# DSP_Block.net
KiCad netlist of a schematic drawn in Altium Designer
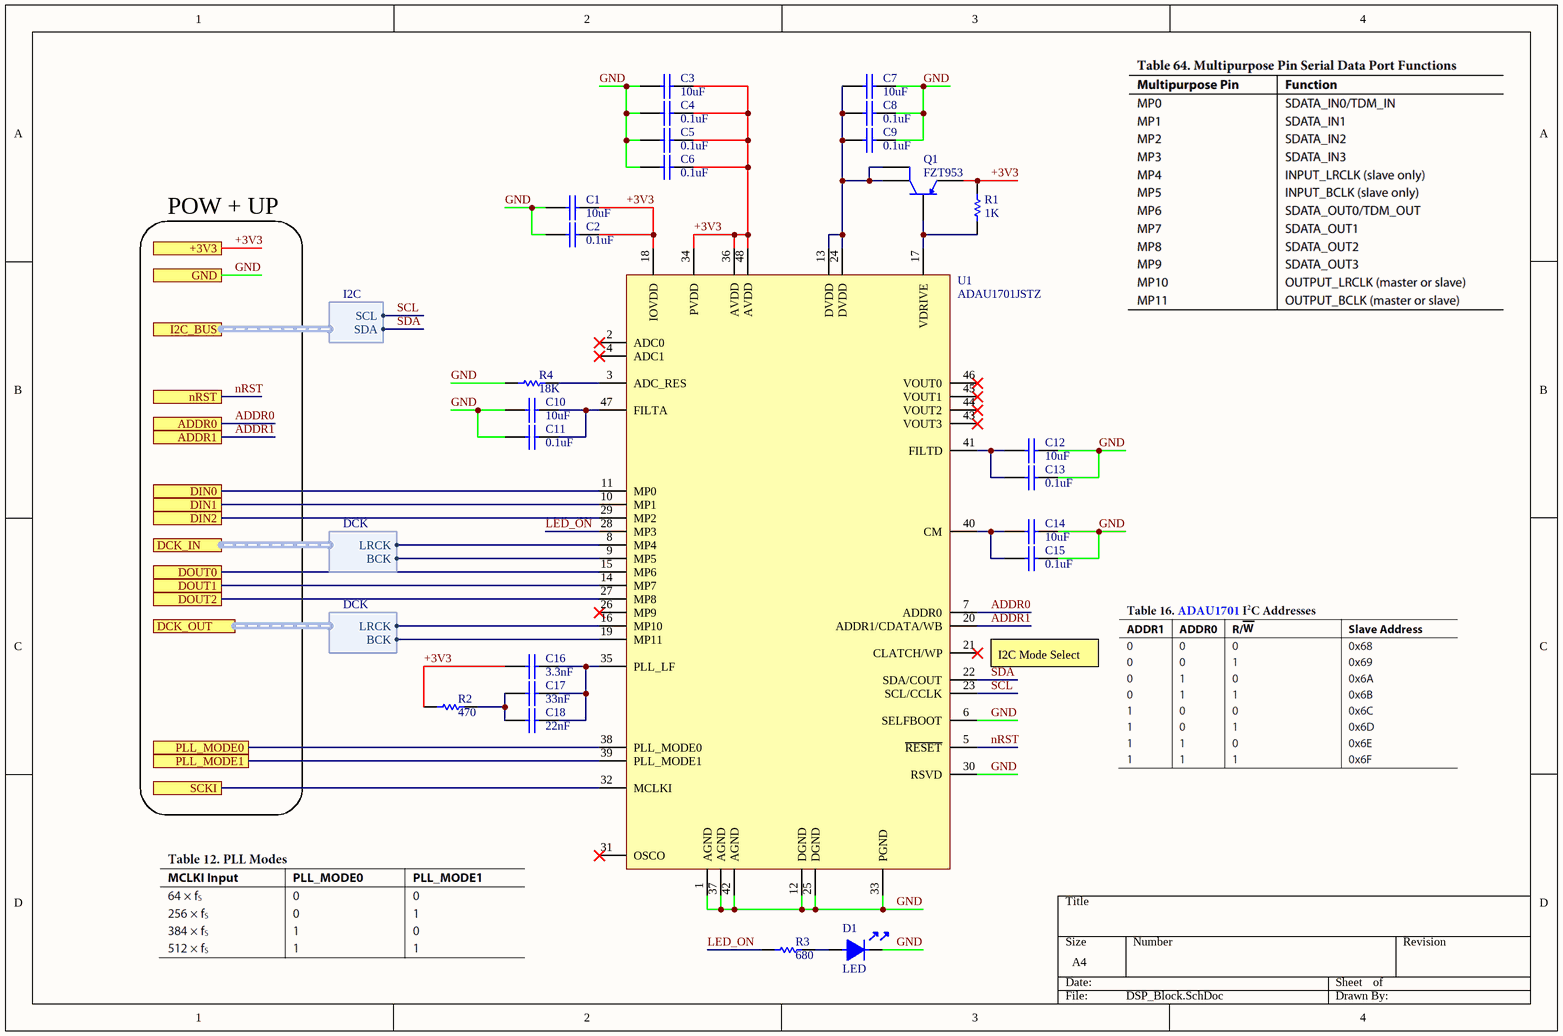
[diagram p0: DSP_Block.SchDoc]

(export (version "E")
  (design (tool "Eeschema 10.0.6"))
  (components
    (comp (ref "C1")
      (value "10uF")
      (footprint "0603-CAP-TDK")
      (libsource (lib "LIB2022 - Passives") (part "CAP-SMD"))
    )
    (comp (ref "C2")
      (value "0.1uF")
      (footprint "0402-CAP-TDK")
      (libsource (lib "LIB2022 - Passives") (part "CAP-SMD"))
    )
    (comp (ref "C3")
      (value "10uF")
      (footprint "0603-CAP-TDK")
      (libsource (lib "LIB2022 - Passives") (part "CAP-SMD"))
    )
    (comp (ref "C4")
      (value "0.1uF")
      (footprint "0402-CAP-TDK")
      (libsource (lib "LIB2022 - Passives") (part "CAP-SMD"))
    )
    (comp (ref "C5")
      (value "0.1uF")
      (footprint "0402-CAP-TDK")
      (libsource (lib "LIB2022 - Passives") (part "CAP-SMD"))
    )
    (comp (ref "C6")
      (value "0.1uF")
      (footprint "0402-CAP-TDK")
      (libsource (lib "LIB2022 - Passives") (part "CAP-SMD"))
    )
    (comp (ref "C7")
      (value "10uF")
      (footprint "0603-CAP-TDK")
      (libsource (lib "LIB2022 - Passives") (part "CAP-SMD"))
    )
    (comp (ref "C8")
      (value "0.1uF")
      (footprint "0402-CAP-TDK")
      (libsource (lib "LIB2022 - Passives") (part "CAP-SMD"))
    )
    (comp (ref "C9")
      (value "0.1uF")
      (footprint "0402-CAP-TDK")
      (libsource (lib "LIB2022 - Passives") (part "CAP-SMD"))
    )
    (comp (ref "C10")
      (value "10uF")
      (footprint "0603-CAP-TDK")
      (libsource (lib "LIB2022 - Passives") (part "CAP-SMD"))
    )
    (comp (ref "C11")
      (value "0.1uF")
      (footprint "0402-CAP-TDK")
      (libsource (lib "LIB2022 - Passives") (part "CAP-SMD"))
    )
    (comp (ref "C12")
      (value "10uF")
      (footprint "0603-CAP-TDK")
      (libsource (lib "LIB2022 - Passives") (part "CAP-SMD"))
    )
    (comp (ref "C13")
      (value "0.1uF")
      (footprint "0402-CAP-TDK")
      (libsource (lib "LIB2022 - Passives") (part "CAP-SMD"))
    )
    (comp (ref "C14")
      (value "10uF")
      (footprint "0603-CAP-TDK")
      (libsource (lib "LIB2022 - Passives") (part "CAP-SMD"))
    )
    (comp (ref "C15")
      (value "0.1uF")
      (footprint "0402-CAP-TDK")
      (libsource (lib "LIB2022 - Passives") (part "CAP-SMD"))
    )
    (comp (ref "C16")
      (value "3.3nF")
      (footprint "0402-CAP-TDK")
      (libsource (lib "LIB2022 - Passives") (part "CAP-SMD"))
    )
    (comp (ref "C17")
      (value "33nF")
      (footprint "0603-CAP-TDK")
      (libsource (lib "LIB2022 - Passives") (part "CAP-SMD"))
    )
    (comp (ref "C18")
      (value "22nF")
      (footprint "0603-CAP-TDK")
      (libsource (lib "LIB2022 - Passives") (part "CAP-SMD"))
    )
    (comp (ref "D1")
      (value "LED")
      (footprint "LED-0805")
      (libsource (lib "LIB2022 - Optoelectronics") (part "LED-SMD"))
    )
    (comp (ref "Q1")
      (value "FZT953")
      (footprint "SOT223-DN")
      (libsource (lib "LIB2022 - Semiconductors") (part "FZT953"))
    )
    (comp (ref "R1")
      (value "1K")
      (footprint "0402-RES-PANASONIC")
      (libsource (lib "LIB2022 - Passives") (part "RES-SMD"))
    )
    (comp (ref "R2")
      (value "470")
      (footprint "0402-RES-PANASONIC")
      (libsource (lib "LIB2022 - Passives") (part "RES-SMD"))
    )
    (comp (ref "R3")
      (value "680")
      (footprint "0402-RES-PANASONIC")
      (libsource (lib "LIB2022 - Passives") (part "RES-SMD"))
    )
    (comp (ref "R4")
      (value "18K")
      (footprint "0402-RES-PANASONIC")
      (libsource (lib "LIB2022 - Passives") (part "RES-SMD"))
    )
    (comp (ref "U1")
      (value "ADAU1701JSTZ")
      (footprint "LQFP-48 - ST-48")
      (description "SigmaDSP 28-/56-Bit Audio Processor with Two ADCs and Four DACs")
      (libsource (lib "LIB2022 - ICs") (part "ADAU1701JSTZ"))
    )
  )
  (nets
    (net (code "3") (name "/+3V3") (class "Default")
      (node (ref "C1") (pin "1") (pinfunction "1_1") (pintype "passive"))
      (node (ref "C16") (pin "1") (pinfunction "1_1") (pintype "passive"))
      (node (ref "C2") (pin "1") (pinfunction "1_1") (pintype "passive"))
      (node (ref "C3") (pin "1") (pinfunction "1_1") (pintype "passive"))
      (node (ref "C4") (pin "1") (pinfunction "1_1") (pintype "passive"))
      (node (ref "C5") (pin "1") (pinfunction "1_1") (pintype "passive"))
      (node (ref "C6") (pin "1") (pinfunction "1_1") (pintype "passive"))
      (node (ref "Q1") (pin "E") (pinfunction "E_E") (pintype "passive"))
      (node (ref "R1") (pin "2") (pinfunction "2_2") (pintype "passive"))
      (node (ref "R2") (pin "1") (pinfunction "1_1") (pintype "passive"))
      (node (ref "U1") (pin "18") (pinfunction "IOVDD_18") (pintype "passive"))
      (node (ref "U1") (pin "34") (pinfunction "PVDD_34") (pintype "passive"))
      (node (ref "U1") (pin "36") (pinfunction "AVDD_36") (pintype "passive"))
      (node (ref "U1") (pin "48") (pinfunction "AVDD_48") (pintype "passive"))
    )
    (net (code "4") (name "/ADDR0") (class "Default")
      (node (ref "U1") (pin "7") (pinfunction "ADDR0_7") (pintype "passive"))
    )
    (net (code "5") (name "/ADDR1") (class "Default")
      (node (ref "U1") (pin "20") (pinfunction "ADDR1/CDATA/WB_20") (pintype "passive"))
    )
    (net (code "6") (name "/DIN0") (class "Default")
      (node (ref "U1") (pin "11") (pinfunction "MP0_11") (pintype "passive"))
    )
    (net (code "7") (name "/DIN1") (class "Default")
      (node (ref "U1") (pin "10") (pinfunction "MP1_10") (pintype "passive"))
    )
    (net (code "8") (name "/DIN2") (class "Default")
      (node (ref "U1") (pin "29") (pinfunction "MP2_29") (pintype "passive"))
    )
    (net (code "9") (name "/DOUT0") (class "Default")
      (node (ref "U1") (pin "15") (pinfunction "MP6_15") (pintype "passive"))
    )
    (net (code "10") (name "/DOUT1") (class "Default")
      (node (ref "U1") (pin "14") (pinfunction "MP7_14") (pintype "passive"))
    )
    (net (code "11") (name "/DOUT2") (class "Default")
      (node (ref "U1") (pin "27") (pinfunction "MP8_27") (pintype "passive"))
    )
    (net (code "12") (name "/GND") (class "Default")
      (node (ref "C1") (pin "2") (pinfunction "2_2") (pintype "passive"))
      (node (ref "C10") (pin "2") (pinfunction "2_2") (pintype "passive"))
      (node (ref "C11") (pin "2") (pinfunction "2_2") (pintype "passive"))
      (node (ref "C12") (pin "1") (pinfunction "1_1") (pintype "passive"))
      (node (ref "C13") (pin "1") (pinfunction "1_1") (pintype "passive"))
      (node (ref "C14") (pin "1") (pinfunction "1_1") (pintype "passive"))
      (node (ref "C15") (pin "1") (pinfunction "1_1") (pintype "passive"))
      (node (ref "C2") (pin "2") (pinfunction "2_2") (pintype "passive"))
      (node (ref "C3") (pin "2") (pinfunction "2_2") (pintype "passive"))
      (node (ref "C4") (pin "2") (pinfunction "2_2") (pintype "passive"))
      (node (ref "C5") (pin "2") (pinfunction "2_2") (pintype "passive"))
      (node (ref "C6") (pin "2") (pinfunction "2_2") (pintype "passive"))
      (node (ref "C7") (pin "1") (pinfunction "1_1") (pintype "passive"))
      (node (ref "C8") (pin "1") (pinfunction "1_1") (pintype "passive"))
      (node (ref "C9") (pin "1") (pinfunction "1_1") (pintype "passive"))
      (node (ref "D1") (pin "2") (pinfunction "2_2") (pintype "passive"))
      (node (ref "R4") (pin "1") (pinfunction "1_1") (pintype "passive"))
      (node (ref "U1") (pin "1") (pinfunction "AGND_1") (pintype "passive"))
      (node (ref "U1") (pin "12") (pinfunction "DGND_12") (pintype "passive"))
      (node (ref "U1") (pin "25") (pinfunction "DGND_25") (pintype "passive"))
      (node (ref "U1") (pin "30") (pinfunction "RSVD_30") (pintype "passive"))
      (node (ref "U1") (pin "33") (pinfunction "PGND_33") (pintype "passive"))
      (node (ref "U1") (pin "37") (pinfunction "AGND_37") (pintype "passive"))
      (node (ref "U1") (pin "42") (pinfunction "AGND_42") (pintype "passive"))
      (node (ref "U1") (pin "6") (pinfunction "SELFBOOT_6") (pintype "passive"))
    )
    (net (code "13") (name "/LED_ON") (class "Default")
      (node (ref "R3") (pin "1") (pinfunction "1_1") (pintype "passive"))
      (node (ref "U1") (pin "28") (pinfunction "MP3_28") (pintype "passive"))
    )
    (net (code "14") (name "/PLL_MODE0") (class "Default")
      (node (ref "U1") (pin "38") (pinfunction "PLL_MODE0_38") (pintype "passive"))
    )
    (net (code "15") (name "/PLL_MODE1") (class "Default")
      (node (ref "U1") (pin "39") (pinfunction "PLL_MODE1_39") (pintype "passive"))
    )
    (net (code "16") (name "/SCKI") (class "Default")
      (node (ref "U1") (pin "32") (pinfunction "MCLKI_32") (pintype "passive"))
    )
    (net (code "17") (name "/SCL") (class "Default")
      (node (ref "U1") (pin "23") (pinfunction "SCL/CCLK_23") (pintype "passive"))
    )
    (net (code "18") (name "/SDA") (class "Default")
      (node (ref "U1") (pin "22") (pinfunction "SDA/COUT_22") (pintype "passive"))
    )
    (net (code "19") (name "/nRST") (class "Default")
      (node (ref "U1") (pin "5") (pinfunction "~{RESET}_5") (pintype "passive"))
    )
    (net (code "22") (name "Net-(C7-Pad2)") (class "Default")
      (node (ref "C7") (pin "2") (pinfunction "2_2") (pintype "passive"))
      (node (ref "C8") (pin "2") (pinfunction "2_2") (pintype "passive"))
      (node (ref "C9") (pin "2") (pinfunction "2_2") (pintype "passive"))
      (node (ref "Q1") (pin "C") (pinfunction "C_C") (pintype "passive"))
      (node (ref "Q1") (pin "C-TAB") (pinfunction "C-TAB_C-TAB") (pintype "passive"))
      (node (ref "U1") (pin "13") (pinfunction "DVDD_13") (pintype "passive"))
      (node (ref "U1") (pin "24") (pinfunction "DVDD_24") (pintype "passive"))
    )
    (net (code "23") (name "Net-(C17-Pad1)") (class "Default")
      (node (ref "C17") (pin "1") (pinfunction "1_1") (pintype "passive"))
      (node (ref "C18") (pin "1") (pinfunction "1_1") (pintype "passive"))
      (node (ref "R2") (pin "2") (pinfunction "2_2") (pintype "passive"))
    )
    (net (code "24") (name "Net-(D1-Pad1)") (class "Default")
      (node (ref "D1") (pin "1") (pinfunction "1_1") (pintype "passive"))
      (node (ref "R3") (pin "2") (pinfunction "2_2") (pintype "passive"))
    )
    (net (code "25") (name "Net-(U1-ADC_RES)") (class "Default")
      (node (ref "R4") (pin "2") (pinfunction "2_2") (pintype "passive"))
      (node (ref "U1") (pin "3") (pinfunction "ADC_RES_3") (pintype "passive"))
    )
    (net (code "26") (name "Net-(U1-CM)") (class "Default")
      (node (ref "C14") (pin "2") (pinfunction "2_2") (pintype "passive"))
      (node (ref "C15") (pin "2") (pinfunction "2_2") (pintype "passive"))
      (node (ref "U1") (pin "40") (pinfunction "CM_40") (pintype "passive"))
    )
    (net (code "27") (name "Net-(U1-FILTA)") (class "Default")
      (node (ref "C10") (pin "1") (pinfunction "1_1") (pintype "passive"))
      (node (ref "C11") (pin "1") (pinfunction "1_1") (pintype "passive"))
      (node (ref "U1") (pin "47") (pinfunction "FILTA_47") (pintype "passive"))
    )
    (net (code "28") (name "Net-(U1-FILTD)") (class "Default")
      (node (ref "C12") (pin "2") (pinfunction "2_2") (pintype "passive"))
      (node (ref "C13") (pin "2") (pinfunction "2_2") (pintype "passive"))
      (node (ref "U1") (pin "41") (pinfunction "FILTD_41") (pintype "passive"))
    )
    (net (code "29") (name "Net-(U1-PLL_LF)") (class "Default")
      (node (ref "C16") (pin "2") (pinfunction "2_2") (pintype "passive"))
      (node (ref "C17") (pin "2") (pinfunction "2_2") (pintype "passive"))
      (node (ref "C18") (pin "2") (pinfunction "2_2") (pintype "passive"))
      (node (ref "U1") (pin "35") (pinfunction "PLL_LF_35") (pintype "passive"))
    )
    (net (code "30") (name "Net-(U1-VDRIVE)") (class "Default")
      (node (ref "Q1") (pin "B") (pinfunction "B_B") (pintype "passive"))
      (node (ref "R1") (pin "1") (pinfunction "1_1") (pintype "passive"))
      (node (ref "U1") (pin "17") (pinfunction "VDRIVE_17") (pintype "passive"))
    )
    (net (code "31") (name "unconnected-(U1-ADC0-Pad2)") (class "Default")
      (node (ref "U1") (pin "2") (pinfunction "ADC0_2") (pintype "passive+no_connect"))
    )
    (net (code "32") (name "unconnected-(U1-ADC1-Pad4)") (class "Default")
      (node (ref "U1") (pin "4") (pinfunction "ADC1_4") (pintype "passive+no_connect"))
    )
    (net (code "33") (name "unconnected-(U1-CLATCH{slash}WP-Pad21)") (class "Default")
      (node (ref "U1") (pin "21") (pinfunction "CLATCH/WP_21") (pintype "passive+no_connect"))
    )
    (net (code "34") (name "unconnected-(U1-MP4-Pad8)") (class "Default")
      (node (ref "U1") (pin "8") (pinfunction "MP4_8") (pintype "passive"))
    )
    (net (code "35") (name "unconnected-(U1-MP5-Pad9)") (class "Default")
      (node (ref "U1") (pin "9") (pinfunction "MP5_9") (pintype "passive"))
    )
    (net (code "36") (name "unconnected-(U1-MP9-Pad26)") (class "Default")
      (node (ref "U1") (pin "26") (pinfunction "MP9_26") (pintype "passive+no_connect"))
    )
    (net (code "37") (name "unconnected-(U1-MP10-Pad16)") (class "Default")
      (node (ref "U1") (pin "16") (pinfunction "MP10_16") (pintype "passive"))
    )
    (net (code "38") (name "unconnected-(U1-MP11-Pad19)") (class "Default")
      (node (ref "U1") (pin "19") (pinfunction "MP11_19") (pintype "passive"))
    )
    (net (code "39") (name "unconnected-(U1-OSCO-Pad31)") (class "Default")
      (node (ref "U1") (pin "31") (pinfunction "OSCO_31") (pintype "passive+no_connect"))
    )
    (net (code "40") (name "unconnected-(U1-VOUT0-Pad46)") (class "Default")
      (node (ref "U1") (pin "46") (pinfunction "VOUT0_46") (pintype "passive+no_connect"))
    )
    (net (code "41") (name "unconnected-(U1-VOUT1-Pad45)") (class "Default")
      (node (ref "U1") (pin "45") (pinfunction "VOUT1_45") (pintype "passive+no_connect"))
    )
    (net (code "42") (name "unconnected-(U1-VOUT2-Pad44)") (class "Default")
      (node (ref "U1") (pin "44") (pinfunction "VOUT2_44") (pintype "passive+no_connect"))
    )
    (net (code "43") (name "unconnected-(U1-VOUT3-Pad43)") (class "Default")
      (node (ref "U1") (pin "43") (pinfunction "VOUT3_43") (pintype "passive+no_connect"))
    )
  )
)
